# incrementeur3b.net
KiCad netlist of a schematic drawn in EAGLE
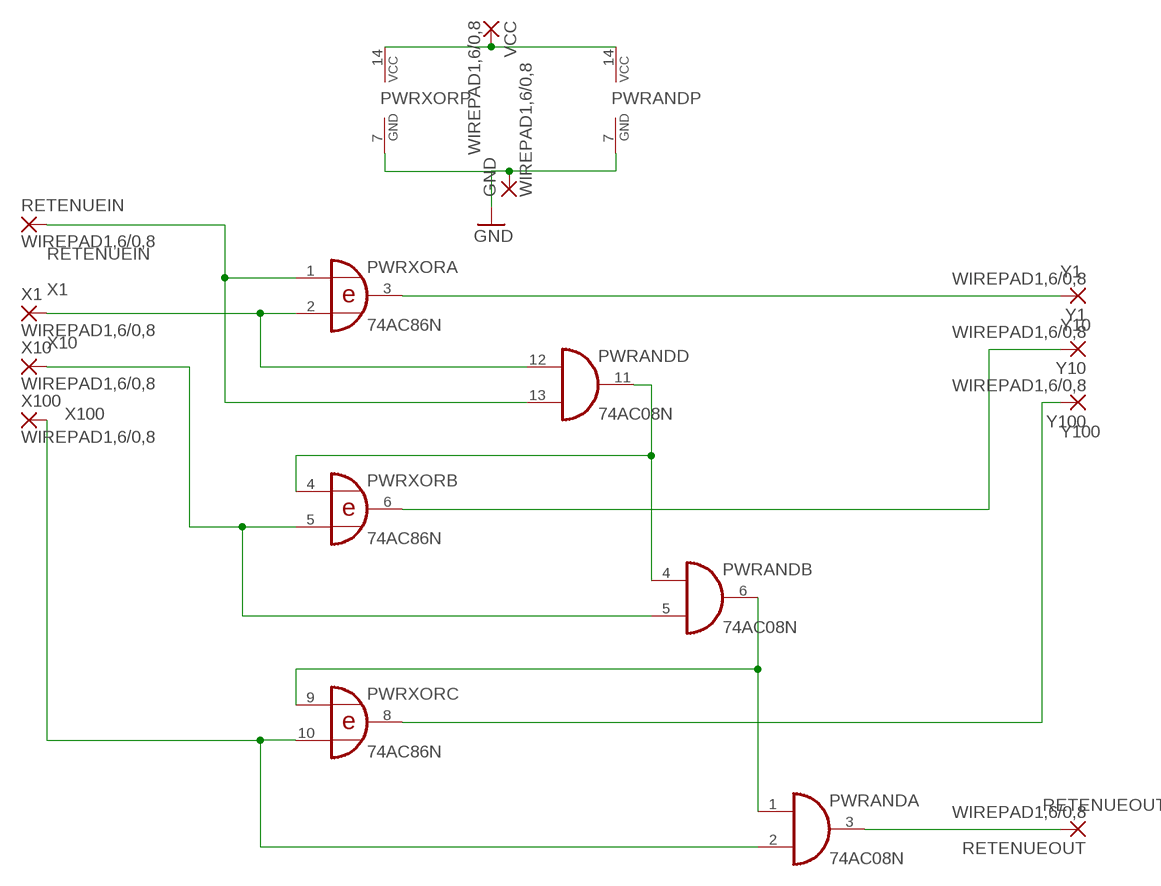
[diagram p0: schematic, sheet 1]

(export (version "E")
  (design (tool "Eeschema 10.0.6"))
  (components
    (comp (ref "GND")
      (value "WIREPAD1,6/0,8")
      (footprint "eagle-import:1,6_0,8")
      (libsource (lib "eagle-import") (part "WIREPAD1,6/0,8"))
    )
    (comp (ref "PWRAND")
      (value "74AC08N")
      (footprint "eagle-import:DIL14")
      (libsource (lib "eagle-import") (part "7408NAC"))
    )
    (comp (ref "PWRXOR")
      (value "74AC86N")
      (footprint "eagle-import:DIL14")
      (libsource (lib "eagle-import") (part "7486NAC"))
    )
    (comp (ref "RETENUEIN")
      (value "WIREPAD1,6/0,8")
      (footprint "eagle-import:1,6_0,8")
      (libsource (lib "eagle-import") (part "WIREPAD1,6/0,8"))
    )
    (comp (ref "RETENUEOUT")
      (value "WIREPAD1,6/0,8")
      (footprint "eagle-import:1,6_0,8")
      (libsource (lib "eagle-import") (part "WIREPAD1,6/0,8"))
    )
    (comp (ref "VCC")
      (value "WIREPAD1,6/0,8")
      (footprint "eagle-import:1,6_0,8")
      (libsource (lib "eagle-import") (part "WIREPAD1,6/0,8"))
    )
    (comp (ref "X1")
      (value "WIREPAD1,6/0,8")
      (footprint "eagle-import:1,6_0,8")
      (libsource (lib "eagle-import") (part "WIREPAD1,6/0,8"))
    )
    (comp (ref "X10")
      (value "WIREPAD1,6/0,8")
      (footprint "eagle-import:1,6_0,8")
      (libsource (lib "eagle-import") (part "WIREPAD1,6/0,8"))
    )
    (comp (ref "X100")
      (value "WIREPAD1,6/0,8")
      (footprint "eagle-import:1,6_0,8")
      (libsource (lib "eagle-import") (part "WIREPAD1,6/0,8"))
    )
    (comp (ref "Y1")
      (value "WIREPAD1,6/0,8")
      (footprint "eagle-import:1,6_0,8")
      (libsource (lib "eagle-import") (part "WIREPAD1,6/0,8"))
    )
    (comp (ref "Y10")
      (value "WIREPAD1,6/0,8")
      (footprint "eagle-import:1,6_0,8")
      (libsource (lib "eagle-import") (part "WIREPAD1,6/0,8"))
    )
    (comp (ref "Y100")
      (value "WIREPAD1,6/0,8")
      (footprint "eagle-import:1,6_0,8")
      (libsource (lib "eagle-import") (part "WIREPAD1,6/0,8"))
    )
  )
  (nets
    (net (code "1") (name "/RETENUEIN") (class "Default")
      (node (ref "PWRAND") (pin "13") (pinfunction "I1_13") (pintype "input"))
      (node (ref "PWRXOR") (pin "1") (pinfunction "I0_1") (pintype "input"))
      (node (ref "RETENUEIN") (pin "1") (pinfunction "P_1") (pintype "passive"))
    )
    (net (code "2") (name "/RETENUEOUT") (class "Default")
      (node (ref "PWRAND") (pin "3") (pinfunction "O_3") (pintype "output"))
      (node (ref "RETENUEOUT") (pin "1") (pinfunction "P_1") (pintype "passive"))
    )
    (net (code "3") (name "/X1") (class "Default")
      (node (ref "PWRAND") (pin "12") (pinfunction "I0_12") (pintype "input"))
      (node (ref "PWRXOR") (pin "2") (pinfunction "I1_2") (pintype "input"))
      (node (ref "X1") (pin "1") (pinfunction "P_1") (pintype "passive"))
    )
    (net (code "4") (name "/X10") (class "Default")
      (node (ref "PWRAND") (pin "5") (pinfunction "I1_5") (pintype "input"))
      (node (ref "PWRXOR") (pin "5") (pinfunction "I1_5") (pintype "input"))
      (node (ref "X10") (pin "1") (pinfunction "P_1") (pintype "passive"))
    )
    (net (code "5") (name "/X100") (class "Default")
      (node (ref "PWRAND") (pin "2") (pinfunction "I1_2") (pintype "input"))
      (node (ref "PWRXOR") (pin "10") (pinfunction "I1_10") (pintype "input"))
      (node (ref "X100") (pin "1") (pinfunction "P_1") (pintype "passive"))
    )
    (net (code "6") (name "/Y1") (class "Default")
      (node (ref "PWRXOR") (pin "3") (pinfunction "O_3") (pintype "output"))
      (node (ref "Y1") (pin "1") (pinfunction "P_1") (pintype "passive"))
    )
    (net (code "7") (name "/Y10") (class "Default")
      (node (ref "PWRXOR") (pin "6") (pinfunction "O_6") (pintype "output"))
      (node (ref "Y10") (pin "1") (pinfunction "P_1") (pintype "passive"))
    )
    (net (code "8") (name "/Y100") (class "Default")
      (node (ref "PWRXOR") (pin "8") (pinfunction "O_8") (pintype "output"))
      (node (ref "Y100") (pin "1") (pinfunction "P_1") (pintype "passive"))
    )
    (net (code "9") (name "GND") (class "Default")
      (node (ref "GND") (pin "1") (pinfunction "P_1") (pintype "passive"))
      (node (ref "PWRAND") (pin "7") (pinfunction "GND_7") (pintype "power_in"))
      (node (ref "PWRXOR") (pin "7") (pinfunction "GND_7") (pintype "power_in"))
    )
    (net (code "10") (name "Net-(PWRANDA-I0)") (class "Default")
      (node (ref "PWRAND") (pin "1") (pinfunction "I0_1") (pintype "input"))
      (node (ref "PWRAND") (pin "6") (pinfunction "O_6") (pintype "output"))
      (node (ref "PWRXOR") (pin "9") (pinfunction "I0_9") (pintype "input"))
    )
    (net (code "11") (name "Net-(PWRANDB-I0)") (class "Default")
      (node (ref "PWRAND") (pin "11") (pinfunction "O_11") (pintype "output"))
      (node (ref "PWRAND") (pin "4") (pinfunction "I0_4") (pintype "input"))
      (node (ref "PWRXOR") (pin "4") (pinfunction "I0_4") (pintype "input"))
    )
    (net (code "12") (name "Net-(PWRANDE-VCC)") (class "Default")
      (node (ref "PWRAND") (pin "14") (pinfunction "VCC_14") (pintype "power_in"))
      (node (ref "PWRXOR") (pin "14") (pinfunction "VCC_14") (pintype "power_in"))
      (node (ref "VCC") (pin "1") (pinfunction "P_1") (pintype "passive"))
    )
  )
)
